# 04_POWER_LDO.net
KiCad netlist of a schematic drawn in Altium Designer
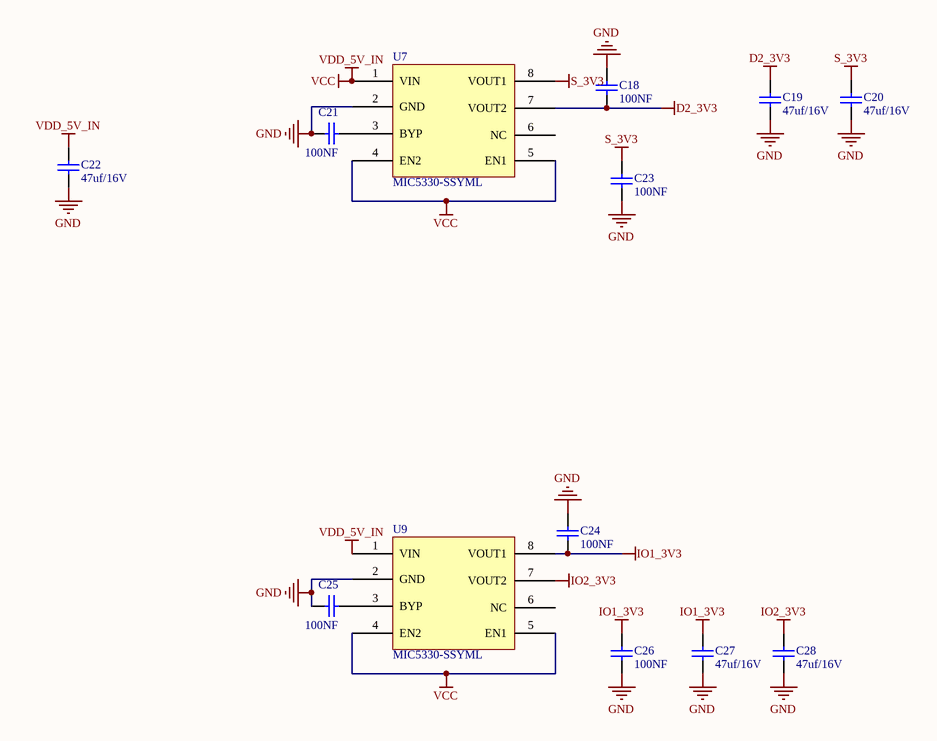
[diagram p0: 04_POWER_LDO.SchDoc]

(export (version "E")
  (design (tool "Eeschema 10.0.6"))
  (components
    (comp (ref "C18")
      (value "100NF")
      (fields (field (name "PUBLISHER") "Altium Limited"))
      (libsource (lib "Miscellaneous Devices") (part "Cap"))
    )
    (comp (ref "C19")
      (value "47uf/16V")
      (description "Capacitor")
      (libsource (lib "Miscellaneous Devices") (part "Cap"))
    )
    (comp (ref "C20")
      (value "47uf/16V")
      (description "Capacitor")
      (libsource (lib "Miscellaneous Devices") (part "Cap"))
    )
    (comp (ref "C21")
      (value "100NF")
      (fields (field (name "PUBLISHER") "Altium Limited"))
      (libsource (lib "Miscellaneous Devices") (part "Cap"))
    )
    (comp (ref "C22")
      (value "47uf/16V")
      (description "Capacitor")
      (libsource (lib "Miscellaneous Devices") (part "Cap"))
    )
    (comp (ref "C23") (value "100NF") (libsource (lib "Miscellaneous Devices") (part "Cap")))
    (comp (ref "C24")
      (value "100NF")
      (fields (field (name "PUBLISHER") "Altium Limited"))
      (libsource (lib "Miscellaneous Devices") (part "Cap"))
    )
    (comp (ref "C25")
      (value "100NF")
      (fields (field (name "PUBLISHER") "Altium Limited"))
      (libsource (lib "Miscellaneous Devices") (part "Cap"))
    )
    (comp (ref "C26") (value "100NF") (libsource (lib "Miscellaneous Devices") (part "Cap")))
    (comp (ref "C27")
      (value "47uf/16V")
      (description "Capacitor")
      (libsource (lib "Miscellaneous Devices") (part "Cap"))
    )
    (comp (ref "C28")
      (value "47uf/16V")
      (description "Capacitor")
      (libsource (lib "Miscellaneous Devices") (part "Cap"))
    )
    (comp (ref "U7") (value "MIC5330-SSYML") (footprint "MIC5530") (libsource (lib "hack") (part "MIC5530")))
    (comp (ref "U9") (value "MIC5330-SSYML") (footprint "MIC5530") (libsource (lib "hack") (part "MIC5530")))
  )
  (nets
    (net (code "1") (name "D2_3V3") (class "Default")
      (node (ref "C18") (pin "1") (pinfunction "1_1") (pintype "passive"))
      (node (ref "C19") (pin "1") (pinfunction "1_1") (pintype "passive"))
      (node (ref "U7") (pin "7") (pinfunction "VOUT2_7") (pintype "passive"))
    )
    (net (code "2") (name "GND") (class "Default")
      (node (ref "C18") (pin "2") (pinfunction "2_2") (pintype "passive"))
      (node (ref "C19") (pin "2") (pinfunction "2_2") (pintype "passive"))
      (node (ref "C20") (pin "2") (pinfunction "2_2") (pintype "passive"))
      (node (ref "C21") (pin "2") (pinfunction "2_2") (pintype "passive"))
      (node (ref "C22") (pin "2") (pinfunction "2_2") (pintype "passive"))
      (node (ref "C23") (pin "1") (pinfunction "1_1") (pintype "passive"))
      (node (ref "C24") (pin "2") (pinfunction "2_2") (pintype "passive"))
      (node (ref "C25") (pin "2") (pinfunction "2_2") (pintype "passive"))
      (node (ref "C26") (pin "1") (pinfunction "1_1") (pintype "passive"))
      (node (ref "C27") (pin "2") (pinfunction "2_2") (pintype "passive"))
      (node (ref "C28") (pin "2") (pinfunction "2_2") (pintype "passive"))
      (node (ref "U7") (pin "2") (pinfunction "GND_2") (pintype "passive"))
      (node (ref "U9") (pin "2") (pinfunction "GND_2") (pintype "passive"))
    )
    (net (code "3") (name "IO1_3V3") (class "Default")
      (node (ref "C24") (pin "1") (pinfunction "1_1") (pintype "passive"))
      (node (ref "C26") (pin "2") (pinfunction "2_2") (pintype "passive"))
      (node (ref "C27") (pin "1") (pinfunction "1_1") (pintype "passive"))
      (node (ref "U9") (pin "8") (pinfunction "VOUT1_8") (pintype "passive"))
    )
    (net (code "4") (name "IO2_3V3") (class "Default")
      (node (ref "C28") (pin "1") (pinfunction "1_1") (pintype "passive"))
      (node (ref "U9") (pin "7") (pinfunction "VOUT2_7") (pintype "passive"))
    )
    (net (code "5") (name "Net-(U7-BYP)") (class "Default")
      (node (ref "C21") (pin "1") (pinfunction "1_1") (pintype "passive"))
      (node (ref "U7") (pin "3") (pinfunction "BYP_3") (pintype "passive"))
    )
    (net (code "6") (name "Net-(U9-BYP)") (class "Default")
      (node (ref "C25") (pin "1") (pinfunction "1_1") (pintype "passive"))
      (node (ref "U9") (pin "3") (pinfunction "BYP_3") (pintype "passive"))
    )
    (net (code "7") (name "S_3V3") (class "Default")
      (node (ref "C20") (pin "1") (pinfunction "1_1") (pintype "passive"))
      (node (ref "C23") (pin "2") (pinfunction "2_2") (pintype "passive"))
      (node (ref "U7") (pin "8") (pinfunction "VOUT1_8") (pintype "passive"))
    )
    (net (code "8") (name "VCC") (class "Default")
      (node (ref "C22") (pin "1") (pinfunction "1_1") (pintype "passive"))
      (node (ref "U7") (pin "1") (pinfunction "VIN_1") (pintype "passive"))
      (node (ref "U7") (pin "4") (pinfunction "EN2_4") (pintype "passive"))
      (node (ref "U7") (pin "5") (pinfunction "EN1_5") (pintype "passive"))
      (node (ref "U9") (pin "1") (pinfunction "VIN_1") (pintype "passive"))
      (node (ref "U9") (pin "4") (pinfunction "EN2_4") (pintype "passive"))
      (node (ref "U9") (pin "5") (pinfunction "EN1_5") (pintype "passive"))
    )
    (net (code "9") (name "unconnected-(U7-NC-Pad6)") (class "Default")
      (node (ref "U7") (pin "6") (pinfunction "NC_6") (pintype "passive"))
    )
    (net (code "10") (name "unconnected-(U9-NC-Pad6)") (class "Default")
      (node (ref "U9") (pin "6") (pinfunction "NC_6") (pintype "passive"))
    )
  )
)
